# micro-circuit-ATMEGA32M1.net
KiCad netlist of a schematic drawn in Altium Designer
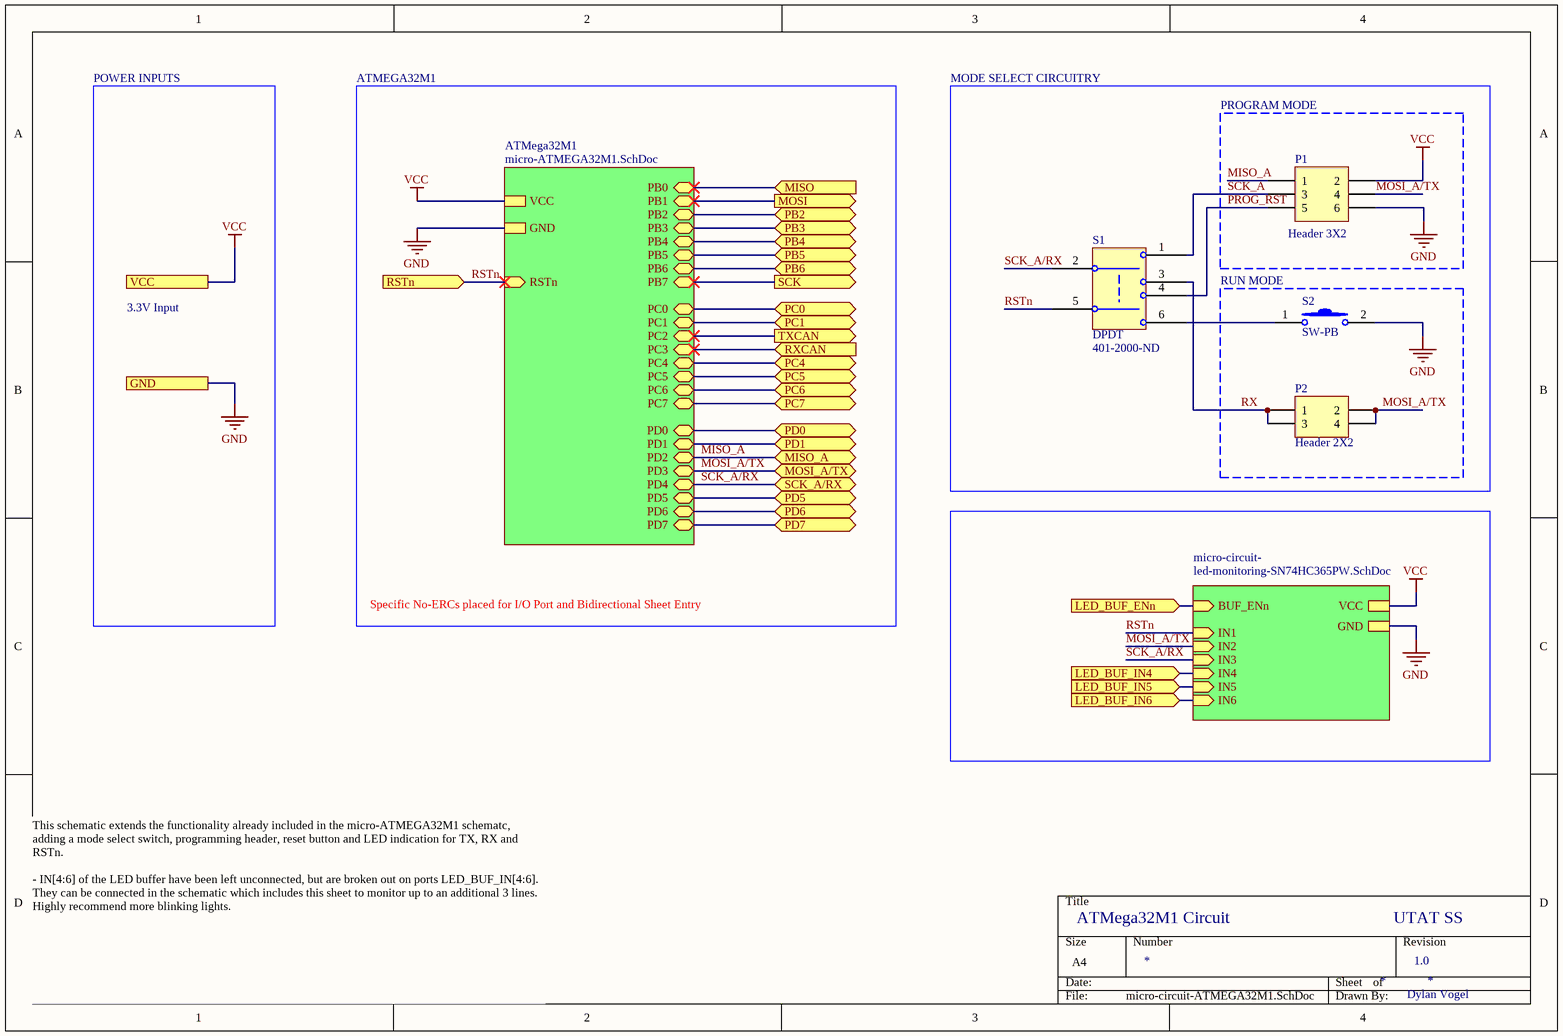
[diagram p0: micro-circuit-ATMEGA32M1.SchDoc]

(export (version "E")
  (design (tool "Eeschema 10.0.6"))
  (components
    (comp (ref "P1")
      (value "Header 3X2")
      (footprint "HDR2X3")
      (description "Header, 3-Pin, Dual row")
      (fields (field (name "PUBLISHER") "Altium Limited"))
      (libsource (lib "Miscellaneous Connectors") (part "Header 3X2"))
    )
    (comp (ref "P2")
      (value "Header 2X2")
      (footprint "HDR2X2")
      (description "Header, 2-Pin, Dual row")
      (fields (field (name "PUBLISHER") "Altium Limited"))
      (libsource (lib "Miscellaneous Connectors") (part "Header 2X2"))
    )
    (comp (ref "S1")
      (value "DPDT")
      (footprint "JS202011AQN - Slide Switch")
      (description "DPDT Switch, customized for the pinout of the JS202011AQN switch.")
      (fields (field (name "SUPPLIER PART NUMBER 1") "401-2000-ND"))
      (libsource (lib "heron-general") (part "DPDT Switch"))
    )
    (comp (ref "S2")
      (value "SW-PB")
      (footprint "PTS830GM140 SMTR LFS - Pushbutton")
      (description "Schematic symbol for a generic 2-pin pushbutton, OFF-mom.")
      (libsource (lib "heron-general") (part "Pushbutton - Low Profile"))
    )
  )
  (nets
    (net (code "6") (name "/MISO_A") (class "Default")
      (node (ref "P1") (pin "1") (pinfunction "1_1") (pintype "passive"))
    )
    (net (code "8") (name "/MOSI_A{slash}TX") (class "Default")
      (node (ref "P1") (pin "4") (pinfunction "4_4") (pintype "passive"))
      (node (ref "P2") (pin "2") (pinfunction "2_2") (pintype "passive"))
      (node (ref "P2") (pin "4") (pinfunction "4_4") (pintype "passive"))
    )
    (net (code "25") (name "/PROG_RST") (class "Default")
      (node (ref "P1") (pin "5") (pinfunction "5_5") (pintype "passive"))
      (node (ref "S1") (pin "4") (pinfunction "POLE2A_4") (pintype "passive"))
    )
    (net (code "26") (name "/RSTn") (class "Default")
      (node (ref "S1") (pin "5") (pinfunction "POLE2_5") (pintype "passive+no_connect"))
    )
    (net (code "27") (name "/RX") (class "Default")
      (node (ref "P2") (pin "1") (pinfunction "1_1") (pintype "passive"))
      (node (ref "P2") (pin "3") (pinfunction "3_3") (pintype "passive"))
      (node (ref "S1") (pin "3") (pinfunction "POLE1B_3") (pintype "passive"))
    )
    (net (code "30") (name "/SCK_A") (class "Default")
      (node (ref "P1") (pin "3") (pinfunction "3_3") (pintype "passive"))
      (node (ref "S1") (pin "1") (pinfunction "POLE1A_1") (pintype "passive"))
    )
    (net (code "31") (name "/SCK_A{slash}RX") (class "Default")
      (node (ref "S1") (pin "2") (pinfunction "POLE1_2") (pintype "passive"))
    )
    (net (code "33") (name "GND") (class "Default")
      (node (ref "P1") (pin "6") (pinfunction "6_6") (pintype "passive"))
      (node (ref "S2") (pin "2") (pinfunction "2_2") (pintype "passive"))
    )
    (net (code "34") (name "Net-(S1-POLE2B)") (class "Default")
      (node (ref "S1") (pin "6") (pinfunction "POLE2B_6") (pintype "passive"))
      (node (ref "S2") (pin "1") (pinfunction "1_1") (pintype "passive"))
    )
    (net (code "35") (name "VCC") (class "Default")
      (node (ref "P1") (pin "2") (pinfunction "2_2") (pintype "passive"))
    )
  )
)
